# rpi64.net
KiCad netlist of a schematic drawn in EAGLE
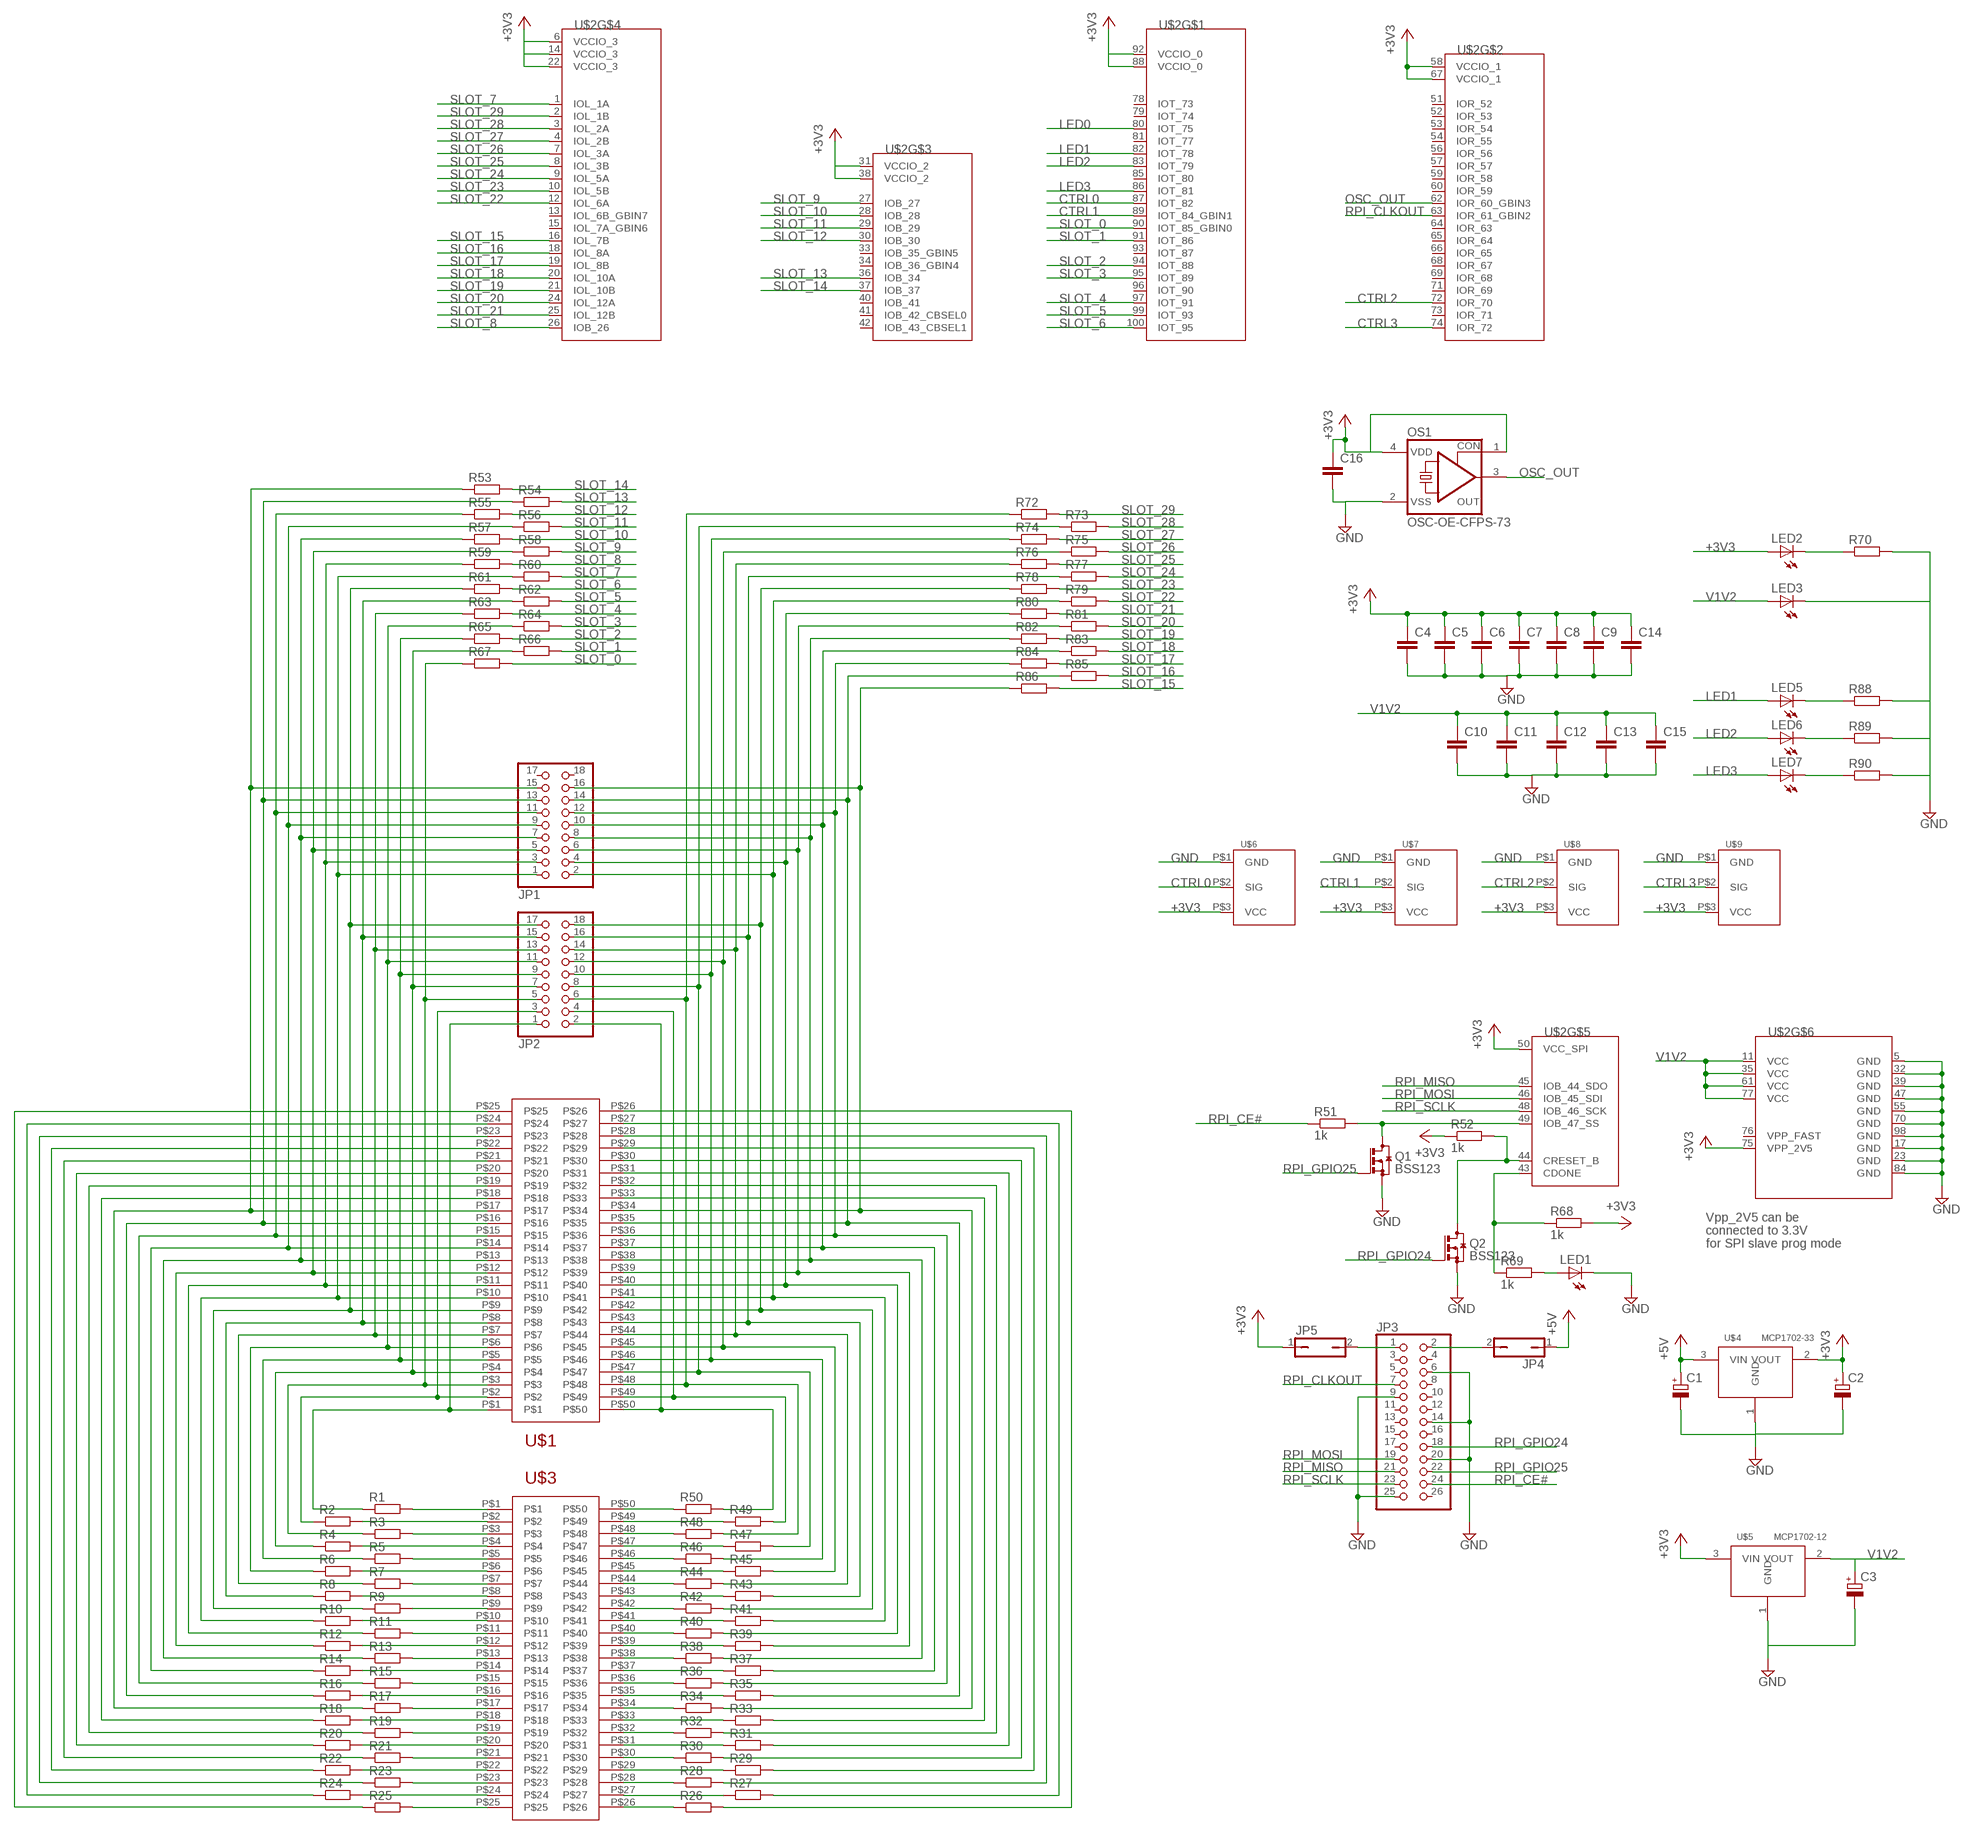
[diagram p0: schematic, sheet 1]

(export (version "E")
  (design (tool "Eeschema 10.0.6"))
  (components
    (comp (ref "C1")
      (value "CPOL-EUR/2012-12R")
      (footprint "eagle-import:R_2012-12R")
      (libsource (lib "eagle-import") (part "CPOL-EUR/2012-12R"))
    )
    (comp (ref "C2")
      (value "CPOL-EUR/2012-12R")
      (footprint "eagle-import:R_2012-12R")
      (libsource (lib "eagle-import") (part "CPOL-EUR/2012-12R"))
    )
    (comp (ref "C3")
      (value "CPOL-EUR/2012-12R")
      (footprint "eagle-import:R_2012-12R")
      (libsource (lib "eagle-import") (part "CPOL-EUR/2012-12R"))
    )
    (comp (ref "C4")
      (value "C-EUC0805")
      (footprint "eagle-import:C0805")
      (libsource (lib "eagle-import") (part "C-EUC0805"))
    )
    (comp (ref "C5")
      (value "C-EUC0805")
      (footprint "eagle-import:C0805")
      (libsource (lib "eagle-import") (part "C-EUC0805"))
    )
    (comp (ref "C6")
      (value "C-EUC0805")
      (footprint "eagle-import:C0805")
      (libsource (lib "eagle-import") (part "C-EUC0805"))
    )
    (comp (ref "C7")
      (value "C-EUC0805")
      (footprint "eagle-import:C0805")
      (libsource (lib "eagle-import") (part "C-EUC0805"))
    )
    (comp (ref "C8")
      (value "C-EUC0805")
      (footprint "eagle-import:C0805")
      (libsource (lib "eagle-import") (part "C-EUC0805"))
    )
    (comp (ref "C9")
      (value "C-EUC0805")
      (footprint "eagle-import:C0805")
      (libsource (lib "eagle-import") (part "C-EUC0805"))
    )
    (comp (ref "C10")
      (value "C-EUC0805")
      (footprint "eagle-import:C0805")
      (libsource (lib "eagle-import") (part "C-EUC0805"))
    )
    (comp (ref "C11")
      (value "C-EUC0805")
      (footprint "eagle-import:C0805")
      (libsource (lib "eagle-import") (part "C-EUC0805"))
    )
    (comp (ref "C12")
      (value "C-EUC0805")
      (footprint "eagle-import:C0805")
      (libsource (lib "eagle-import") (part "C-EUC0805"))
    )
    (comp (ref "C13")
      (value "C-EUC0805")
      (footprint "eagle-import:C0805")
      (libsource (lib "eagle-import") (part "C-EUC0805"))
    )
    (comp (ref "C14")
      (value "C-EUC0805")
      (footprint "eagle-import:C0805")
      (libsource (lib "eagle-import") (part "C-EUC0805"))
    )
    (comp (ref "C15")
      (value "C-EUC0805")
      (footprint "eagle-import:C0805")
      (libsource (lib "eagle-import") (part "C-EUC0805"))
    )
    (comp (ref "C16")
      (value "C-EUC0805")
      (footprint "eagle-import:C0805")
      (libsource (lib "eagle-import") (part "C-EUC0805"))
    )
    (comp (ref "JP1")
      (value "PINHD-2X9")
      (footprint "eagle-import:2X09")
      (libsource (lib "eagle-import") (part "PINHD-2X9"))
    )
    (comp (ref "JP2")
      (value "PINHD-2X9")
      (footprint "eagle-import:2X09")
      (libsource (lib "eagle-import") (part "PINHD-2X9"))
    )
    (comp (ref "JP3")
      (value "PINHD-2X13")
      (footprint "eagle-import:2X13")
      (libsource (lib "eagle-import") (part "PINHD-2X13"))
    )
    (comp (ref "JP4")
      (value "JP1Q")
      (footprint "eagle-import:JP1")
      (libsource (lib "eagle-import") (part "JP1Q"))
    )
    (comp (ref "JP5")
      (value "JP1Q")
      (footprint "eagle-import:JP1")
      (libsource (lib "eagle-import") (part "JP1Q"))
    )
    (comp (ref "LED1")
      (value "LEDCHIPLED_0603")
      (footprint "eagle-import:CHIPLED_0603")
      (libsource (lib "eagle-import") (part "LEDCHIPLED_0603"))
    )
    (comp (ref "LED2")
      (value "LEDCHIPLED_0603")
      (footprint "eagle-import:CHIPLED_0603")
      (libsource (lib "eagle-import") (part "LEDCHIPLED_0603"))
    )
    (comp (ref "LED3")
      (value "LEDCHIPLED_0603")
      (footprint "eagle-import:CHIPLED_0603")
      (libsource (lib "eagle-import") (part "LEDCHIPLED_0603"))
    )
    (comp (ref "LED5")
      (value "LEDCHIPLED_0603")
      (footprint "eagle-import:CHIPLED_0603")
      (libsource (lib "eagle-import") (part "LEDCHIPLED_0603"))
    )
    (comp (ref "LED6")
      (value "LEDCHIPLED_0603")
      (footprint "eagle-import:CHIPLED_0603")
      (libsource (lib "eagle-import") (part "LEDCHIPLED_0603"))
    )
    (comp (ref "LED7")
      (value "LEDCHIPLED_0603")
      (footprint "eagle-import:CHIPLED_0603")
      (libsource (lib "eagle-import") (part "LEDCHIPLED_0603"))
    )
    (comp (ref "OS1")
      (value "OSC-OE-CFPS-73")
      (footprint "eagle-import:7.2X5.2-4-PAD")
      (libsource (lib "eagle-import") (part "OSC-OE-CFPS-73"))
    )
    (comp (ref "Q1")
      (value "BSS123")
      (footprint "eagle-import:SOT23")
      (libsource (lib "eagle-import") (part "BSS123"))
    )
    (comp (ref "Q2")
      (value "BSS123")
      (footprint "eagle-import:SOT23")
      (libsource (lib "eagle-import") (part "BSS123"))
    )
    (comp (ref "R1")
      (value "R-EU_R0603")
      (footprint "eagle-import:R0603")
      (libsource (lib "eagle-import") (part "R-EU_R0603"))
    )
    (comp (ref "R2")
      (value "R-EU_R0603")
      (footprint "eagle-import:R0603")
      (libsource (lib "eagle-import") (part "R-EU_R0603"))
    )
    (comp (ref "R3")
      (value "R-EU_R0603")
      (footprint "eagle-import:R0603")
      (libsource (lib "eagle-import") (part "R-EU_R0603"))
    )
    (comp (ref "R4")
      (value "R-EU_R0603")
      (footprint "eagle-import:R0603")
      (libsource (lib "eagle-import") (part "R-EU_R0603"))
    )
    (comp (ref "R5")
      (value "R-EU_R0603")
      (footprint "eagle-import:R0603")
      (libsource (lib "eagle-import") (part "R-EU_R0603"))
    )
    (comp (ref "R6")
      (value "R-EU_R0603")
      (footprint "eagle-import:R0603")
      (libsource (lib "eagle-import") (part "R-EU_R0603"))
    )
    (comp (ref "R7")
      (value "R-EU_R0603")
      (footprint "eagle-import:R0603")
      (libsource (lib "eagle-import") (part "R-EU_R0603"))
    )
    (comp (ref "R8")
      (value "R-EU_R0603")
      (footprint "eagle-import:R0603")
      (libsource (lib "eagle-import") (part "R-EU_R0603"))
    )
    (comp (ref "R9")
      (value "R-EU_R0603")
      (footprint "eagle-import:R0603")
      (libsource (lib "eagle-import") (part "R-EU_R0603"))
    )
    (comp (ref "R10")
      (value "R-EU_R0603")
      (footprint "eagle-import:R0603")
      (libsource (lib "eagle-import") (part "R-EU_R0603"))
    )
    (comp (ref "R11")
      (value "R-EU_R0603")
      (footprint "eagle-import:R0603")
      (libsource (lib "eagle-import") (part "R-EU_R0603"))
    )
    (comp (ref "R12")
      (value "R-EU_R0603")
      (footprint "eagle-import:R0603")
      (libsource (lib "eagle-import") (part "R-EU_R0603"))
    )
    (comp (ref "R13")
      (value "R-EU_R0603")
      (footprint "eagle-import:R0603")
      (libsource (lib "eagle-import") (part "R-EU_R0603"))
    )
    (comp (ref "R14")
      (value "R-EU_R0603")
      (footprint "eagle-import:R0603")
      (libsource (lib "eagle-import") (part "R-EU_R0603"))
    )
    (comp (ref "R15")
      (value "R-EU_R0603")
      (footprint "eagle-import:R0603")
      (libsource (lib "eagle-import") (part "R-EU_R0603"))
    )
    (comp (ref "R16")
      (value "R-EU_R0603")
      (footprint "eagle-import:R0603")
      (libsource (lib "eagle-import") (part "R-EU_R0603"))
    )
    (comp (ref "R17")
      (value "R-EU_R0603")
      (footprint "eagle-import:R0603")
      (libsource (lib "eagle-import") (part "R-EU_R0603"))
    )
    (comp (ref "R18")
      (value "R-EU_R0603")
      (footprint "eagle-import:R0603")
      (libsource (lib "eagle-import") (part "R-EU_R0603"))
    )
    (comp (ref "R19")
      (value "R-EU_R0603")
      (footprint "eagle-import:R0603")
      (libsource (lib "eagle-import") (part "R-EU_R0603"))
    )
    (comp (ref "R20")
      (value "R-EU_R0603")
      (footprint "eagle-import:R0603")
      (libsource (lib "eagle-import") (part "R-EU_R0603"))
    )
    (comp (ref "R21")
      (value "R-EU_R0603")
      (footprint "eagle-import:R0603")
      (libsource (lib "eagle-import") (part "R-EU_R0603"))
    )
    (comp (ref "R22")
      (value "R-EU_R0603")
      (footprint "eagle-import:R0603")
      (libsource (lib "eagle-import") (part "R-EU_R0603"))
    )
    (comp (ref "R23")
      (value "R-EU_R0603")
      (footprint "eagle-import:R0603")
      (libsource (lib "eagle-import") (part "R-EU_R0603"))
    )
    (comp (ref "R24")
      (value "R-EU_R0603")
      (footprint "eagle-import:R0603")
      (libsource (lib "eagle-import") (part "R-EU_R0603"))
    )
    (comp (ref "R25")
      (value "R-EU_R0603")
      (footprint "eagle-import:R0603")
      (libsource (lib "eagle-import") (part "R-EU_R0603"))
    )
    (comp (ref "R26")
      (value "R-EU_R0603")
      (footprint "eagle-import:R0603")
      (libsource (lib "eagle-import") (part "R-EU_R0603"))
    )
    (comp (ref "R27")
      (value "R-EU_R0603")
      (footprint "eagle-import:R0603")
      (libsource (lib "eagle-import") (part "R-EU_R0603"))
    )
    (comp (ref "R28")
      (value "R-EU_R0603")
      (footprint "eagle-import:R0603")
      (libsource (lib "eagle-import") (part "R-EU_R0603"))
    )
    (comp (ref "R29")
      (value "R-EU_R0603")
      (footprint "eagle-import:R0603")
      (libsource (lib "eagle-import") (part "R-EU_R0603"))
    )
    (comp (ref "R30")
      (value "R-EU_R0603")
      (footprint "eagle-import:R0603")
      (libsource (lib "eagle-import") (part "R-EU_R0603"))
    )
    (comp (ref "R31")
      (value "R-EU_R0603")
      (footprint "eagle-import:R0603")
      (libsource (lib "eagle-import") (part "R-EU_R0603"))
    )
    (comp (ref "R32")
      (value "R-EU_R0603")
      (footprint "eagle-import:R0603")
      (libsource (lib "eagle-import") (part "R-EU_R0603"))
    )
    (comp (ref "R33")
      (value "R-EU_R0603")
      (footprint "eagle-import:R0603")
      (libsource (lib "eagle-import") (part "R-EU_R0603"))
    )
    (comp (ref "R34")
      (value "R-EU_R0603")
      (footprint "eagle-import:R0603")
      (libsource (lib "eagle-import") (part "R-EU_R0603"))
    )
    (comp (ref "R35")
      (value "R-EU_R0603")
      (footprint "eagle-import:R0603")
      (libsource (lib "eagle-import") (part "R-EU_R0603"))
    )
    (comp (ref "R36")
      (value "R-EU_R0603")
      (footprint "eagle-import:R0603")
      (libsource (lib "eagle-import") (part "R-EU_R0603"))
    )
    (comp (ref "R37")
      (value "R-EU_R0603")
      (footprint "eagle-import:R0603")
      (libsource (lib "eagle-import") (part "R-EU_R0603"))
    )
    (comp (ref "R38")
      (value "R-EU_R0603")
      (footprint "eagle-import:R0603")
      (libsource (lib "eagle-import") (part "R-EU_R0603"))
    )
    (comp (ref "R39")
      (value "R-EU_R0603")
      (footprint "eagle-import:R0603")
      (libsource (lib "eagle-import") (part "R-EU_R0603"))
    )
    (comp (ref "R40")
      (value "R-EU_R0603")
      (footprint "eagle-import:R0603")
      (libsource (lib "eagle-import") (part "R-EU_R0603"))
    )
    (comp (ref "R41")
      (value "R-EU_R0603")
      (footprint "eagle-import:R0603")
      (libsource (lib "eagle-import") (part "R-EU_R0603"))
    )
    (comp (ref "R42")
      (value "R-EU_R0603")
      (footprint "eagle-import:R0603")
      (libsource (lib "eagle-import") (part "R-EU_R0603"))
    )
    (comp (ref "R43")
      (value "R-EU_R0603")
      (footprint "eagle-import:R0603")
      (libsource (lib "eagle-import") (part "R-EU_R0603"))
    )
    (comp (ref "R44")
      (value "R-EU_R0603")
      (footprint "eagle-import:R0603")
      (libsource (lib "eagle-import") (part "R-EU_R0603"))
    )
    (comp (ref "R45")
      (value "R-EU_R0603")
      (footprint "eagle-import:R0603")
      (libsource (lib "eagle-import") (part "R-EU_R0603"))
    )
    (comp (ref "R46")
      (value "R-EU_R0603")
      (footprint "eagle-import:R0603")
      (libsource (lib "eagle-import") (part "R-EU_R0603"))
    )
    (comp (ref "R47")
      (value "R-EU_R0603")
      (footprint "eagle-import:R0603")
      (libsource (lib "eagle-import") (part "R-EU_R0603"))
    )
    (comp (ref "R48")
      (value "R-EU_R0603")
      (footprint "eagle-import:R0603")
      (libsource (lib "eagle-import") (part "R-EU_R0603"))
    )
    (comp (ref "R49")
      (value "R-EU_R0603")
      (footprint "eagle-import:R0603")
      (libsource (lib "eagle-import") (part "R-EU_R0603"))
    )
    (comp (ref "R50")
      (value "R-EU_R0603")
      (footprint "eagle-import:R0603")
      (libsource (lib "eagle-import") (part "R-EU_R0603"))
    )
    (comp (ref "R51")
      (value "1k")
      (footprint "eagle-import:R0603")
      (libsource (lib "eagle-import") (part "R-EU_R0603"))
    )
    (comp (ref "R52")
      (value "1k")
      (footprint "eagle-import:R0603")
      (libsource (lib "eagle-import") (part "R-EU_R0603"))
    )
    (comp (ref "R53")
      (value "R-EU_R0603")
      (footprint "eagle-import:R0603")
      (libsource (lib "eagle-import") (part "R-EU_R0603"))
    )
    (comp (ref "R54")
      (value "R-EU_R0603")
      (footprint "eagle-import:R0603")
      (libsource (lib "eagle-import") (part "R-EU_R0603"))
    )
    (comp (ref "R55")
      (value "R-EU_R0603")
      (footprint "eagle-import:R0603")
      (libsource (lib "eagle-import") (part "R-EU_R0603"))
    )
    (comp (ref "R56")
      (value "R-EU_R0603")
      (footprint "eagle-import:R0603")
      (libsource (lib "eagle-import") (part "R-EU_R0603"))
    )
    (comp (ref "R57")
      (value "R-EU_R0603")
      (footprint "eagle-import:R0603")
      (libsource (lib "eagle-import") (part "R-EU_R0603"))
    )
    (comp (ref "R58")
      (value "R-EU_R0603")
      (footprint "eagle-import:R0603")
      (libsource (lib "eagle-import") (part "R-EU_R0603"))
    )
    (comp (ref "R59")
      (value "R-EU_R0603")
      (footprint "eagle-import:R0603")
      (libsource (lib "eagle-import") (part "R-EU_R0603"))
    )
    (comp (ref "R60")
      (value "R-EU_R0603")
      (footprint "eagle-import:R0603")
      (libsource (lib "eagle-import") (part "R-EU_R0603"))
    )
    (comp (ref "R61")
      (value "R-EU_R0603")
      (footprint "eagle-import:R0603")
      (libsource (lib "eagle-import") (part "R-EU_R0603"))
    )
    (comp (ref "R62")
      (value "R-EU_R0603")
      (footprint "eagle-import:R0603")
      (libsource (lib "eagle-import") (part "R-EU_R0603"))
    )
    (comp (ref "R63")
      (value "R-EU_R0603")
      (footprint "eagle-import:R0603")
      (libsource (lib "eagle-import") (part "R-EU_R0603"))
    )
    (comp (ref "R64")
      (value "R-EU_R0603")
      (footprint "eagle-import:R0603")
      (libsource (lib "eagle-import") (part "R-EU_R0603"))
    )
    (comp (ref "R65")
      (value "R-EU_R0603")
      (footprint "eagle-import:R0603")
      (libsource (lib "eagle-import") (part "R-EU_R0603"))
    )
    (comp (ref "R66")
      (value "R-EU_R0603")
      (footprint "eagle-import:R0603")
      (libsource (lib "eagle-import") (part "R-EU_R0603"))
    )
    (comp (ref "R67")
      (value "R-EU_R0603")
      (footprint "eagle-import:R0603")
      (libsource (lib "eagle-import") (part "R-EU_R0603"))
    )
    (comp (ref "R68")
      (value "1k")
      (footprint "eagle-import:R0603")
      (libsource (lib "eagle-import") (part "R-EU_R0603"))
    )
    (comp (ref "R69")
      (value "1k")
      (footprint "eagle-import:R0603")
      (libsource (lib "eagle-import") (part "R-EU_R0603"))
    )
    (comp (ref "R70")
      (value "R-EU_R0603")
      (footprint "eagle-import:R0603")
      (libsource (lib "eagle-import") (part "R-EU_R0603"))
    )
    (comp (ref "R72")
      (value "R-EU_R0603")
      (footprint "eagle-import:R0603")
      (libsource (lib "eagle-import") (part "R-EU_R0603"))
    )
    (comp (ref "R73")
      (value "R-EU_R0603")
      (footprint "eagle-import:R0603")
      (libsource (lib "eagle-import") (part "R-EU_R0603"))
    )
    (comp (ref "R74")
      (value "R-EU_R0603")
      (footprint "eagle-import:R0603")
      (libsource (lib "eagle-import") (part "R-EU_R0603"))
    )
    (comp (ref "R75")
      (value "R-EU_R0603")
      (footprint "eagle-import:R0603")
      (libsource (lib "eagle-import") (part "R-EU_R0603"))
    )
    (comp (ref "R76")
      (value "R-EU_R0603")
      (footprint "eagle-import:R0603")
      (libsource (lib "eagle-import") (part "R-EU_R0603"))
    )
    (comp (ref "R77")
      (value "R-EU_R0603")
      (footprint "eagle-import:R0603")
      (libsource (lib "eagle-import") (part "R-EU_R0603"))
    )
    (comp (ref "R78")
      (value "R-EU_R0603")
      (footprint "eagle-import:R0603")
      (libsource (lib "eagle-import") (part "R-EU_R0603"))
    )
    (comp (ref "R79")
      (value "R-EU_R0603")
      (footprint "eagle-import:R0603")
      (libsource (lib "eagle-import") (part "R-EU_R0603"))
    )
    (comp (ref "R80")
      (value "R-EU_R0603")
      (footprint "eagle-import:R0603")
      (libsource (lib "eagle-import") (part "R-EU_R0603"))
    )
    (comp (ref "R81")
      (value "R-EU_R0603")
      (footprint "eagle-import:R0603")
      (libsource (lib "eagle-import") (part "R-EU_R0603"))
    )
    (comp (ref "R82")
      (value "R-EU_R0603")
      (footprint "eagle-import:R0603")
      (libsource (lib "eagle-import") (part "R-EU_R0603"))
    )
    (comp (ref "R83")
      (value "R-EU_R0603")
      (footprint "eagle-import:R0603")
      (libsource (lib "eagle-import") (part "R-EU_R0603"))
    )
    (comp (ref "R84")
      (value "R-EU_R0603")
      (footprint "eagle-import:R0603")
      (libsource (lib "eagle-import") (part "R-EU_R0603"))
    )
    (comp (ref "R85")
      (value "R-EU_R0603")
      (footprint "eagle-import:R0603")
      (libsource (lib "eagle-import") (part "R-EU_R0603"))
    )
    (comp (ref "R86")
      (value "R-EU_R0603")
      (footprint "eagle-import:R0603")
      (libsource (lib "eagle-import") (part "R-EU_R0603"))
    )
    (comp (ref "R88")
      (value "R-EU_R0603")
      (footprint "eagle-import:R0603")
      (libsource (lib "eagle-import") (part "R-EU_R0603"))
    )
    (comp (ref "R89")
      (value "R-EU_R0603")
      (footprint "eagle-import:R0603")
      (libsource (lib "eagle-import") (part "R-EU_R0603"))
    )
    (comp (ref "R90")
      (value "R-EU_R0603")
      (footprint "eagle-import:R0603")
      (libsource (lib "eagle-import") (part "R-EU_R0603"))
    )
    (comp (ref "U$1")
      (value "5530843-5")
      (footprint "eagle-import:5530843-3")
      (libsource (lib "eagle-import") (part "5530843-5"))
    )
    (comp (ref "U$2")
      (value "ICE40HX1KVQ100")
      (footprint "eagle-import:VQ100")
      (libsource (lib "eagle-import") (part "ICE40HX1KVQ100"))
    )
    (comp (ref "U$3")
      (value "EDGE50")
      (footprint "eagle-import:EDGE50")
      (libsource (lib "eagle-import") (part "EDGE50"))
    )
    (comp (ref "U$4")
      (value "MCP1702-33")
      (footprint "eagle-import:SOT23A")
      (libsource (lib "eagle-import") (part "MCP1702"))
    )
    (comp (ref "U$5")
      (value "MCP1702-12")
      (footprint "eagle-import:SOT23A")
      (libsource (lib "eagle-import") (part "MCP1702"))
    )
    (comp (ref "U$6")
      (value "N64_CONTROLER")
      (footprint "eagle-import:N64_CONTROLER")
      (libsource (lib "eagle-import") (part "N64_CONTROLER"))
    )
    (comp (ref "U$7")
      (value "N64_CONTROLER")
      (footprint "eagle-import:N64_CONTROLER")
      (libsource (lib "eagle-import") (part "N64_CONTROLER"))
    )
    (comp (ref "U$8")
      (value "N64_CONTROLER")
      (footprint "eagle-import:N64_CONTROLER")
      (libsource (lib "eagle-import") (part "N64_CONTROLER"))
    )
    (comp (ref "U$9")
      (value "N64_CONTROLER")
      (footprint "eagle-import:N64_CONTROLER")
      (libsource (lib "eagle-import") (part "N64_CONTROLER"))
    )
  )
  (nets
    (net (code "1") (name "+3V3") (class "Default")
      (node (ref "C14") (pin "1") (pinfunction "1_1") (pintype "passive"))
      (node (ref "C16") (pin "1") (pinfunction "1_1") (pintype "passive"))
      (node (ref "C2") (pin "+") (pinfunction "+_+") (pintype "passive"))
      (node (ref "C4") (pin "1") (pinfunction "1_1") (pintype "passive"))
      (node (ref "C5") (pin "1") (pinfunction "1_1") (pintype "passive"))
      (node (ref "C6") (pin "1") (pinfunction "1_1") (pintype "passive"))
      (node (ref "C7") (pin "1") (pinfunction "1_1") (pintype "passive"))
      (node (ref "C8") (pin "1") (pinfunction "1_1") (pintype "passive"))
      (node (ref "C9") (pin "1") (pinfunction "1_1") (pintype "passive"))
      (node (ref "JP5") (pin "1") (pinfunction "1_1") (pintype "passive"))
      (node (ref "LED2") (pin "A") (pinfunction "A_A") (pintype "passive"))
      (node (ref "OS1") (pin "1") (pinfunction "CON_1") (pintype "input"))
      (node (ref "OS1") (pin "4") (pinfunction "VDD_4") (pintype "power_in"))
      (node (ref "R52") (pin "1") (pinfunction "1_1") (pintype "passive"))
      (node (ref "R68") (pin "2") (pinfunction "2_2") (pintype "passive"))
      (node (ref "U$2") (pin "14") (pinfunction "VCCIO_3_14") (pintype "power_in"))
      (node (ref "U$2") (pin "22") (pinfunction "VCCIO_3_22") (pintype "power_in"))
      (node (ref "U$2") (pin "31") (pinfunction "VCCIO_2_31") (pintype "power_in"))
      (node (ref "U$2") (pin "38") (pinfunction "VCCIO_2_38") (pintype "power_in"))
      (node (ref "U$2") (pin "50") (pinfunction "VCC_SPI_50") (pintype "power_in"))
      (node (ref "U$2") (pin "58") (pinfunction "VCCIO_1_58") (pintype "power_in"))
      (node (ref "U$2") (pin "6") (pinfunction "VCCIO_3_6") (pintype "power_in"))
      (node (ref "U$2") (pin "67") (pinfunction "VCCIO_1_67") (pintype "power_in"))
      (node (ref "U$2") (pin "75") (pinfunction "VPP_2V5_75") (pintype "power_in"))
      (node (ref "U$2") (pin "88") (pinfunction "VCCIO_0_88") (pintype "power_in"))
      (node (ref "U$2") (pin "92") (pinfunction "VCCIO_0_92") (pintype "power_in"))
      (node (ref "U$4") (pin "2") (pinfunction "VOUT_2") (pintype "bidirectional"))
      (node (ref "U$5") (pin "3") (pinfunction "VIN_3") (pintype "bidirectional"))
      (node (ref "U$6") (pin "P$3") (pinfunction "VCC_P$3") (pintype "power_in"))
      (node (ref "U$7") (pin "P$3") (pinfunction "VCC_P$3") (pintype "power_in"))
      (node (ref "U$8") (pin "P$3") (pinfunction "VCC_P$3") (pintype "power_in"))
      (node (ref "U$9") (pin "P$3") (pinfunction "VCC_P$3") (pintype "power_in"))
    )
    (net (code "2") (name "+5V") (class "Default")
      (node (ref "C1") (pin "+") (pinfunction "+_+") (pintype "passive"))
      (node (ref "JP4") (pin "1") (pinfunction "1_1") (pintype "passive"))
      (node (ref "U$4") (pin "3") (pinfunction "VIN_3") (pintype "bidirectional"))
    )
    (net (code "3") (name "/CTRL0") (class "Default")
      (node (ref "U$2") (pin "87") (pinfunction "IOT_82_87") (pintype "bidirectional"))
      (node (ref "U$6") (pin "P$2") (pinfunction "SIG_P$2") (pintype "power_in"))
    )
    (net (code "4") (name "/CTRL1") (class "Default")
      (node (ref "U$2") (pin "89") (pinfunction "IOT_84_GBIN1_89") (pintype "bidirectional"))
      (node (ref "U$7") (pin "P$2") (pinfunction "SIG_P$2") (pintype "power_in"))
    )
    (net (code "5") (name "/CTRL2") (class "Default")
      (node (ref "U$2") (pin "72") (pinfunction "IOR_70_72") (pintype "bidirectional"))
      (node (ref "U$8") (pin "P$2") (pinfunction "SIG_P$2") (pintype "power_in"))
    )
    (net (code "6") (name "/CTRL3") (class "Default")
      (node (ref "U$2") (pin "74") (pinfunction "IOR_72_74") (pintype "bidirectional"))
      (node (ref "U$9") (pin "P$2") (pinfunction "SIG_P$2") (pintype "power_in"))
    )
    (net (code "7") (name "/LED0") (class "Default")
      (node (ref "U$2") (pin "80") (pinfunction "IOT_75_80") (pintype "bidirectional"))
    )
    (net (code "8") (name "/LED1") (class "Default")
      (node (ref "LED5") (pin "A") (pinfunction "A_A") (pintype "passive"))
      (node (ref "U$2") (pin "82") (pinfunction "IOT_78_82") (pintype "bidirectional"))
    )
    (net (code "9") (name "/LED2") (class "Default")
      (node (ref "LED6") (pin "A") (pinfunction "A_A") (pintype "passive"))
      (node (ref "U$2") (pin "83") (pinfunction "IOT_79_83") (pintype "bidirectional"))
    )
    (net (code "10") (name "/LED3") (class "Default")
      (node (ref "LED7") (pin "A") (pinfunction "A_A") (pintype "passive"))
      (node (ref "U$2") (pin "86") (pinfunction "IOT_81_86") (pintype "bidirectional"))
    )
    (net (code "11") (name "/OSC_OUT") (class "Default")
      (node (ref "OS1") (pin "3") (pinfunction "OUT_3") (pintype "output"))
      (node (ref "U$2") (pin "62") (pinfunction "IOR_60_GBIN3_62") (pintype "bidirectional"))
    )
    (net (code "12") (name "/RPI_CE#") (class "Default")
      (node (ref "JP3") (pin "24") (pinfunction "24_24") (pintype "passive"))
      (node (ref "R51") (pin "1") (pinfunction "1_1") (pintype "passive"))
    )
    (net (code "13") (name "/RPI_CLKOUT") (class "Default")
      (node (ref "JP3") (pin "7") (pinfunction "7_7") (pintype "passive"))
      (node (ref "U$2") (pin "63") (pinfunction "IOR_61_GBIN2_63") (pintype "bidirectional"))
    )
    (net (code "14") (name "/RPI_GPIO24") (class "Default")
      (node (ref "JP3") (pin "18") (pinfunction "18_18") (pintype "passive"))
      (node (ref "Q2") (pin "1") (pinfunction "G_1") (pintype "passive"))
    )
    (net (code "15") (name "/RPI_GPIO25") (class "Default")
      (node (ref "JP3") (pin "22") (pinfunction "22_22") (pintype "passive"))
      (node (ref "Q1") (pin "1") (pinfunction "G_1") (pintype "passive"))
    )
    (net (code "16") (name "/RPI_MISO") (class "Default")
      (node (ref "JP3") (pin "21") (pinfunction "21_21") (pintype "passive"))
      (node (ref "U$2") (pin "45") (pinfunction "IOB_44_SDO_45") (pintype "bidirectional"))
    )
    (net (code "17") (name "/RPI_MOSI") (class "Default")
      (node (ref "JP3") (pin "19") (pinfunction "19_19") (pintype "passive"))
      (node (ref "U$2") (pin "46") (pinfunction "IOB_45_SDI_46") (pintype "bidirectional"))
    )
    (net (code "18") (name "/RPI_SCLK") (class "Default")
      (node (ref "JP3") (pin "23") (pinfunction "23_23") (pintype "passive"))
      (node (ref "U$2") (pin "48") (pinfunction "IOB_46_SCK_48") (pintype "bidirectional"))
    )
    (net (code "19") (name "/SLOT_0") (class "Default")
      (node (ref "R67") (pin "2") (pinfunction "2_2") (pintype "passive"))
      (node (ref "U$2") (pin "90") (pinfunction "IOT_85_GBIN0_90") (pintype "bidirectional"))
    )
    (net (code "20") (name "/SLOT_1") (class "Default")
      (node (ref "R66") (pin "2") (pinfunction "2_2") (pintype "passive"))
      (node (ref "U$2") (pin "91") (pinfunction "IOT_86_91") (pintype "bidirectional"))
    )
    (net (code "21") (name "/SLOT_2") (class "Default")
      (node (ref "R65") (pin "2") (pinfunction "2_2") (pintype "passive"))
      (node (ref "U$2") (pin "94") (pinfunction "IOT_88_94") (pintype "bidirectional"))
    )
    (net (code "22") (name "/SLOT_3") (class "Default")
      (node (ref "R64") (pin "2") (pinfunction "2_2") (pintype "passive"))
      (node (ref "U$2") (pin "95") (pinfunction "IOT_89_95") (pintype "bidirectional"))
    )
    (net (code "23") (name "/SLOT_4") (class "Default")
      (node (ref "R63") (pin "2") (pinfunction "2_2") (pintype "passive"))
      (node (ref "U$2") (pin "97") (pinfunction "IOT_91_97") (pintype "bidirectional"))
    )
    (net (code "24") (name "/SLOT_5") (class "Default")
      (node (ref "R62") (pin "2") (pinfunction "2_2") (pintype "passive"))
      (node (ref "U$2") (pin "99") (pinfunction "IOT_93_99") (pintype "bidirectional"))
    )
    (net (code "25") (name "/SLOT_6") (class "Default")
      (node (ref "R61") (pin "2") (pinfunction "2_2") (pintype "passive"))
      (node (ref "U$2") (pin "100") (pinfunction "IOT_95_100") (pintype "bidirectional"))
    )
    (net (code "26") (name "/SLOT_7") (class "Default")
      (node (ref "R60") (pin "2") (pinfunction "2_2") (pintype "passive"))
      (node (ref "U$2") (pin "1") (pinfunction "IOL_1A_1") (pintype "bidirectional"))
    )
    (net (code "27") (name "/SLOT_8") (class "Default")
      (node (ref "R59") (pin "2") (pinfunction "2_2") (pintype "passive"))
      (node (ref "U$2") (pin "26") (pinfunction "IOB_26_26") (pintype "bidirectional"))
    )
    (net (code "28") (name "/SLOT_9") (class "Default")
      (node (ref "R58") (pin "2") (pinfunction "2_2") (pintype "passive"))
      (node (ref "U$2") (pin "27") (pinfunction "IOB_27_27") (pintype "bidirectional"))
    )
    (net (code "29") (name "/SLOT_10") (class "Default")
      (node (ref "R57") (pin "2") (pinfunction "2_2") (pintype "passive"))
      (node (ref "U$2") (pin "28") (pinfunction "IOB_28_28") (pintype "bidirectional"))
    )
    (net (code "30") (name "/SLOT_11") (class "Default")
      (node (ref "R56") (pin "2") (pinfunction "2_2") (pintype "passive"))
      (node (ref "U$2") (pin "29") (pinfunction "IOB_29_29") (pintype "bidirectional"))
    )
    (net (code "31") (name "/SLOT_12") (class "Default")
      (node (ref "R55") (pin "2") (pinfunction "2_2") (pintype "passive"))
      (node (ref "U$2") (pin "30") (pinfunction "IOB_30_30") (pintype "bidirectional"))
    )
    (net (code "32") (name "/SLOT_13") (class "Default")
      (node (ref "R54") (pin "2") (pinfunction "2_2") (pintype "passive"))
      (node (ref "U$2") (pin "36") (pinfunction "IOB_34_36") (pintype "bidirectional"))
    )
    (net (code "33") (name "/SLOT_14") (class "Default")
      (node (ref "R53") (pin "2") (pinfunction "2_2") (pintype "passive"))
      (node (ref "U$2") (pin "37") (pinfunction "IOB_37_37") (pintype "bidirectional"))
    )
    (net (code "34") (name "/SLOT_15") (class "Default")
      (node (ref "R86") (pin "2") (pinfunction "2_2") (pintype "passive"))
      (node (ref "U$2") (pin "16") (pinfunction "IOL_7B_16") (pintype "bidirectional"))
    )
    (net (code "35") (name "/SLOT_16") (class "Default")
      (node (ref "R85") (pin "2") (pinfunction "2_2") (pintype "passive"))
      (node (ref "U$2") (pin "18") (pinfunction "IOL_8A_18") (pintype "bidirectional"))
    )
    (net (code "36") (name "/SLOT_17") (class "Default")
      (node (ref "R84") (pin "2") (pinfunction "2_2") (pintype "passive"))
      (node (ref "U$2") (pin "19") (pinfunction "IOL_8B_19") (pintype "bidirectional"))
    )
    (net (code "37") (name "/SLOT_18") (class "Default")
      (node (ref "R83") (pin "2") (pinfunction "2_2") (pintype "passive"))
      (node (ref "U$2") (pin "20") (pinfunction "IOL_10A_20") (pintype "bidirectional"))
    )
    (net (code "38") (name "/SLOT_19") (class "Default")
      (node (ref "R82") (pin "2") (pinfunction "2_2") (pintype "passive"))
      (node (ref "U$2") (pin "21") (pinfunction "IOL_10B_21") (pintype "bidirectional"))
    )
    (net (code "39") (name "/SLOT_20") (class "Default")
      (node (ref "R81") (pin "2") (pinfunction "2_2") (pintype "passive"))
      (node (ref "U$2") (pin "24") (pinfunction "IOL_12A_24") (pintype "bidirectional"))
    )
    (net (code "40") (name "/SLOT_21") (class "Default")
      (node (ref "R80") (pin "2") (pinfunction "2_2") (pintype "passive"))
      (node (ref "U$2") (pin "25") (pinfunction "IOL_12B_25") (pintype "bidirectional"))
    )
    (net (code "41") (name "/SLOT_22") (class "Default")
      (node (ref "R79") (pin "2") (pinfunction "2_2") (pintype "passive"))
      (node (ref "U$2") (pin "12") (pinfunction "IOL_6A_12") (pintype "bidirectional"))
    )
    (net (code "42") (name "/SLOT_23") (class "Default")
      (node (ref "R78") (pin "2") (pinfunction "2_2") (pintype "passive"))
      (node (ref "U$2") (pin "10") (pinfunction "IOL_5B_10") (pintype "bidirectional"))
    )
    (net (code "43") (name "/SLOT_24") (class "Default")
      (node (ref "R77") (pin "2") (pinfunction "2_2") (pintype "passive"))
      (node (ref "U$2") (pin "9") (pinfunction "IOL_5A_9") (pintype "bidirectional"))
    )
    (net (code "44") (name "/SLOT_25") (class "Default")
      (node (ref "R76") (pin "2") (pinfunction "2_2") (pintype "passive"))
      (node (ref "U$2") (pin "8") (pinfunction "IOL_3B_8") (pintype "bidirectional"))
    )
    (net (code "45") (name "/SLOT_26") (class "Default")
      (node (ref "R75") (pin "2") (pinfunction "2_2") (pintype "passive"))
      (node (ref "U$2") (pin "7") (pinfunction "IOL_3A_7") (pintype "bidirectional"))
    )
    (net (code "46") (name "/SLOT_27") (class "Default")
      (node (ref "R74") (pin "2") (pinfunction "2_2") (pintype "passive"))
      (node (ref "U$2") (pin "4") (pinfunction "IOL_2B_4") (pintype "bidirectional"))
    )
    (net (code "47") (name "/SLOT_28") (class "Default")
      (node (ref "R73") (pin "2") (pinfunction "2_2") (pintype "passive"))
      (node (ref "U$2") (pin "3") (pinfunction "IOL_2A_3") (pintype "bidirectional"))
    )
    (net (code "48") (name "/SLOT_29") (class "Default")
      (node (ref "R72") (pin "2") (pinfunction "2_2") (pintype "passive"))
      (node (ref "U$2") (pin "2") (pinfunction "IOL_1B_2") (pintype "bidirectional"))
    )
    (net (code "49") (name "/V1V2") (class "Default")
      (node (ref "C10") (pin "1") (pinfunction "1_1") (pintype "passive"))
      (node (ref "C11") (pin "1") (pinfunction "1_1") (pintype "passive"))
      (node (ref "C12") (pin "1") (pinfunction "1_1") (pintype "passive"))
      (node (ref "C13") (pin "1") (pinfunction "1_1") (pintype "passive"))
      (node (ref "C15") (pin "1") (pinfunction "1_1") (pintype "passive"))
      (node (ref "C3") (pin "+") (pinfunction "+_+") (pintype "passive"))
      (node (ref "LED3") (pin "A") (pinfunction "A_A") (pintype "passive"))
      (node (ref "U$2") (pin "11") (pinfunction "VCC_11") (pintype "power_in"))
      (node (ref "U$2") (pin "35") (pinfunction "VCC_35") (pintype "power_in"))
      (node (ref "U$2") (pin "61") (pinfunction "VCC_61") (pintype "power_in"))
      (node (ref "U$2") (pin "77") (pinfunction "VCC_77") (pintype "power_in"))
      (node (ref "U$5") (pin "2") (pinfunction "VOUT_2") (pintype "bidirectional"))
    )
    (net (code "50") (name "/VPP_FAST") (class "Default")
      (node (ref "U$2") (pin "76") (pinfunction "VPP_FAST_76") (pintype "power_in"))
    )
    (net (code "51") (name "GND") (class "Default")
      (node (ref "C1") (pin "-") (pinfunction "-_-") (pintype "passive"))
      (node (ref "C10") (pin "2") (pinfunction "2_2") (pintype "passive"))
      (node (ref "C11") (pin "2") (pinfunction "2_2") (pintype "passive"))
      (node (ref "C12") (pin "2") (pinfunction "2_2") (pintype "passive"))
      (node (ref "C13") (pin "2") (pinfunction "2_2") (pintype "passive"))
      (node (ref "C14") (pin "2") (pinfunction "2_2") (pintype "passive"))
      (node (ref "C15") (pin "2") (pinfunction "2_2") (pintype "passive"))
      (node (ref "C16") (pin "2") (pinfunction "2_2") (pintype "passive"))
      (node (ref "C2") (pin "-") (pinfunction "-_-") (pintype "passive"))
      (node (ref "C3") (pin "-") (pinfunction "-_-") (pintype "passive"))
      (node (ref "C4") (pin "2") (pinfunction "2_2") (pintype "passive"))
      (node (ref "C5") (pin "2") (pinfunction "2_2") (pintype "passive"))
      (node (ref "C6") (pin "2") (pinfunction "2_2") (pintype "passive"))
      (node (ref "C7") (pin "2") (pinfunction "2_2") (pintype "passive"))
      (node (ref "C8") (pin "2") (pinfunction "2_2") (pintype "passive"))
      (node (ref "C9") (pin "2") (pinfunction "2_2") (pintype "passive"))
      (node (ref "JP3") (pin "14") (pinfunction "14_14") (pintype "passive"))
      (node (ref "JP3") (pin "20") (pinfunction "20_20") (pintype "passive"))
      (node (ref "JP3") (pin "25") (pinfunction "25_25") (pintype "passive"))
      (node (ref "JP3") (pin "6") (pinfunction "6_6") (pintype "passive"))
      (node (ref "JP3") (pin "9") (pinfunction "9_9") (pintype "passive"))
      (node (ref "LED1") (pin "C") (pinfunction "C_C") (pintype "passive"))
      (node (ref "LED3") (pin "C") (pinfunction "C_C") (pintype "passive"))
      (node (ref "OS1") (pin "2") (pinfunction "VSS_2") (pintype "power_in"))
      (node (ref "Q1") (pin "2") (pinfunction "S_2") (pintype "passive"))
      (node (ref "Q2") (pin "2") (pinfunction "S_2") (pintype "passive"))
      (node (ref "R70") (pin "2") (pinfunction "2_2") (pintype "passive"))
      (node (ref "R88") (pin "2") (pinfunction "2_2") (pintype "passive"))
      (node (ref "R89") (pin "2") (pinfunction "2_2") (pintype "passive"))
      (node (ref "R90") (pin "2") (pinfunction "2_2") (pintype "passive"))
      (node (ref "U$2") (pin "17") (pinfunction "GND_17") (pintype "power_in"))
      (node (ref "U$2") (pin "23") (pinfunction "GND_23") (pintype "power_in"))
      (node (ref "U$2") (pin "32") (pinfunction "GND_32") (pintype "power_in"))
      (node (ref "U$2") (pin "39") (pinfunction "GND_39") (pintype "power_in"))
      (node (ref "U$2") (pin "47") (pinfunction "GND_47") (pintype "power_in"))
      (node (ref "U$2") (pin "5") (pinfunction "GND_5") (pintype "power_in"))
      (node (ref "U$2") (pin "55") (pinfunction "GND_55") (pintype "power_in"))
      (node (ref "U$2") (pin "70") (pinfunction "GND_70") (pintype "power_in"))
      (node (ref "U$2") (pin "84") (pinfunction "GND_84") (pintype "power_in"))
      (node (ref "U$2") (pin "98") (pinfunction "GND_98") (pintype "power_in"))
      (node (ref "U$4") (pin "1") (pinfunction "GND_1") (pintype "bidirectional"))
      (node (ref "U$5") (pin "1") (pinfunction "GND_1") (pintype "bidirectional"))
      (node (ref "U$6") (pin "P$1") (pinfunction "GND_P$1") (pintype "power_in"))
      (node (ref "U$7") (pin "P$1") (pinfunction "GND_P$1") (pintype "power_in"))
      (node (ref "U$8") (pin "P$1") (pinfunction "GND_P$1") (pintype "power_in"))
      (node (ref "U$9") (pin "P$1") (pinfunction "GND_P$1") (pintype "power_in"))
    )
    (net (code "52") (name "Net-(JP1-Pad1)") (class "Default")
      (node (ref "JP1") (pin "1") (pinfunction "1_1") (pintype "passive"))
      (node (ref "R10") (pin "1") (pinfunction "1_1") (pintype "passive"))
      (node (ref "R60") (pin "1") (pinfunction "1_1") (pintype "passive"))
      (node (ref "U$1") (pin "P$10") (pinfunction "P$10_P$10") (pintype "bidirectional"))
    )
    (net (code "53") (name "Net-(JP1-Pad2)") (class "Default")
      (node (ref "JP1") (pin "2") (pinfunction "2_2") (pintype "passive"))
      (node (ref "R41") (pin "2") (pinfunction "2_2") (pintype "passive"))
      (node (ref "R79") (pin "1") (pinfunction "1_1") (pintype "passive"))
      (node (ref "U$1") (pin "P$41") (pinfunction "P$41_P$41") (pintype "bidirectional"))
    )
    (net (code "54") (name "Net-(JP1-Pad3)") (class "Default")
      (node (ref "JP1") (pin "3") (pinfunction "3_3") (pintype "passive"))
      (node (ref "R11") (pin "1") (pinfunction "1_1") (pintype "passive"))
      (node (ref "R59") (pin "1") (pinfunction "1_1") (pintype "passive"))
      (node (ref "U$1") (pin "P$11") (pinfunction "P$11_P$11") (pintype "bidirectional"))
    )
    (net (code "55") (name "Net-(JP1-Pad4)") (class "Default")
      (node (ref "JP1") (pin "4") (pinfunction "4_4") (pintype "passive"))
      (node (ref "R40") (pin "2") (pinfunction "2_2") (pintype "passive"))
      (node (ref "R80") (pin "1") (pinfunction "1_1") (pintype "passive"))
      (node (ref "U$1") (pin "P$40") (pinfunction "P$40_P$40") (pintype "bidirectional"))
    )
    (net (code "56") (name "Net-(JP1-Pad5)") (class "Default")
      (node (ref "JP1") (pin "5") (pinfunction "5_5") (pintype "passive"))
      (node (ref "R12") (pin "1") (pinfunction "1_1") (pintype "passive"))
      (node (ref "R58") (pin "1") (pinfunction "1_1") (pintype "passive"))
      (node (ref "U$1") (pin "P$12") (pinfunction "P$12_P$12") (pintype "bidirectional"))
    )
    (net (code "57") (name "Net-(JP1-Pad6)") (class "Default")
      (node (ref "JP1") (pin "6") (pinfunction "6_6") (pintype "passive"))
      (node (ref "R39") (pin "2") (pinfunction "2_2") (pintype "passive"))
      (node (ref "R81") (pin "1") (pinfunction "1_1") (pintype "passive"))
      (node (ref "U$1") (pin "P$39") (pinfunction "P$39_P$39") (pintype "bidirectional"))
    )
    (net (code "58") (name "Net-(JP1-Pad7)") (class "Default")
      (node (ref "JP1") (pin "7") (pinfunction "7_7") (pintype "passive"))
      (node (ref "R13") (pin "1") (pinfunction "1_1") (pintype "passive"))
      (node (ref "R57") (pin "1") (pinfunction "1_1") (pintype "passive"))
      (node (ref "U$1") (pin "P$13") (pinfunction "P$13_P$13") (pintype "bidirectional"))
    )
    (net (code "59") (name "Net-(JP1-Pad8)") (class "Default")
      (node (ref "JP1") (pin "8") (pinfunction "8_8") (pintype "passive"))
      (node (ref "R38") (pin "2") (pinfunction "2_2") (pintype "passive"))
      (node (ref "R82") (pin "1") (pinfunction "1_1") (pintype "passive"))
      (node (ref "U$1") (pin "P$38") (pinfunction "P$38_P$38") (pintype "bidirectional"))
    )
    (net (code "60") (name "Net-(JP1-Pad9)") (class "Default")
      (node (ref "JP1") (pin "9") (pinfunction "9_9") (pintype "passive"))
      (node (ref "R14") (pin "1") (pinfunction "1_1") (pintype "passive"))
      (node (ref "R56") (pin "1") (pinfunction "1_1") (pintype "passive"))
      (node (ref "U$1") (pin "P$14") (pinfunction "P$14_P$14") (pintype "bidirectional"))
    )
    (net (code "61") (name "Net-(JP1-Pad10)") (class "Default")
      (node (ref "JP1") (pin "10") (pinfunction "10_10") (pintype "passive"))
      (node (ref "R37") (pin "2") (pinfunction "2_2") (pintype "passive"))
      (node (ref "R83") (pin "1") (pinfunction "1_1") (pintype "passive"))
      (node (ref "U$1") (pin "P$37") (pinfunction "P$37_P$37") (pintype "bidirectional"))
    )
    (net (code "62") (name "Net-(JP1-Pad11)") (class "Default")
      (node (ref "JP1") (pin "11") (pinfunction "11_11") (pintype "passive"))
      (node (ref "R15") (pin "1") (pinfunction "1_1") (pintype "passive"))
      (node (ref "R55") (pin "1") (pinfunction "1_1") (pintype "passive"))
      (node (ref "U$1") (pin "P$15") (pinfunction "P$15_P$15") (pintype "bidirectional"))
    )
    (net (code "63") (name "Net-(JP1-Pad12)") (class "Default")
      (node (ref "JP1") (pin "12") (pinfunction "12_12") (pintype "passive"))
      (node (ref "R36") (pin "2") (pinfunction "2_2") (pintype "passive"))
      (node (ref "R84") (pin "1") (pinfunction "1_1") (pintype "passive"))
      (node (ref "U$1") (pin "P$36") (pinfunction "P$36_P$36") (pintype "bidirectional"))
    )
    (net (code "64") (name "Net-(JP1-Pad13)") (class "Default")
      (node (ref "JP1") (pin "13") (pinfunction "13_13") (pintype "passive"))
      (node (ref "R16") (pin "1") (pinfunction "1_1") (pintype "passive"))
      (node (ref "R54") (pin "1") (pinfunction "1_1") (pintype "passive"))
      (node (ref "U$1") (pin "P$16") (pinfunction "P$16_P$16") (pintype "bidirectional"))
    )
    (net (code "65") (name "Net-(JP1-Pad14)") (class "Default")
      (node (ref "JP1") (pin "14") (pinfunction "14_14") (pintype "passive"))
      (node (ref "R35") (pin "2") (pinfunction "2_2") (pintype "passive"))
      (node (ref "R85") (pin "1") (pinfunction "1_1") (pintype "passive"))
      (node (ref "U$1") (pin "P$35") (pinfunction "P$35_P$35") (pintype "bidirectional"))
    )
    (net (code "66") (name "Net-(JP1-Pad15)") (class "Default")
      (node (ref "JP1") (pin "15") (pinfunction "15_15") (pintype "passive"))
      (node (ref "R17") (pin "1") (pinfunction "1_1") (pintype "passive"))
      (node (ref "R53") (pin "1") (pinfunction "1_1") (pintype "passive"))
      (node (ref "U$1") (pin "P$17") (pinfunction "P$17_P$17") (pintype "bidirectional"))
    )
    (net (code "67") (name "Net-(JP1-Pad16)") (class "Default")
      (node (ref "JP1") (pin "16") (pinfunction "16_16") (pintype "passive"))
      (node (ref "R34") (pin "2") (pinfunction "2_2") (pintype "passive"))
      (node (ref "R86") (pin "1") (pinfunction "1_1") (pintype "passive"))
      (node (ref "U$1") (pin "P$34") (pinfunction "P$34_P$34") (pintype "bidirectional"))
    )
    (net (code "68") (name "Net-(JP2-Pad1)") (class "Default")
      (node (ref "JP2") (pin "1") (pinfunction "1_1") (pintype "passive"))
      (node (ref "R1") (pin "1") (pinfunction "1_1") (pintype "passive"))
      (node (ref "U$1") (pin "P$1") (pinfunction "P$1_P$1") (pintype "bidirectional"))
    )
    (net (code "69") (name "Net-(JP2-Pad2)") (class "Default")
      (node (ref "JP2") (pin "2") (pinfunction "2_2") (pintype "passive"))
      (node (ref "R50") (pin "2") (pinfunction "2_2") (pintype "passive"))
      (node (ref "U$1") (pin "P$50") (pinfunction "P$50_P$50") (pintype "bidirectional"))
    )
    (net (code "70") (name "Net-(JP2-Pad3)") (class "Default")
      (node (ref "JP2") (pin "3") (pinfunction "3_3") (pintype "passive"))
      (node (ref "R2") (pin "1") (pinfunction "1_1") (pintype "passive"))
      (node (ref "U$1") (pin "P$2") (pinfunction "P$2_P$2") (pintype "bidirectional"))
    )
    (net (code "71") (name "Net-(JP2-Pad4)") (class "Default")
      (node (ref "JP2") (pin "4") (pinfunction "4_4") (pintype "passive"))
      (node (ref "R49") (pin "2") (pinfunction "2_2") (pintype "passive"))
      (node (ref "U$1") (pin "P$49") (pinfunction "P$49_P$49") (pintype "bidirectional"))
    )
    (net (code "72") (name "Net-(JP2-Pad5)") (class "Default")
      (node (ref "JP2") (pin "5") (pinfunction "5_5") (pintype "passive"))
      (node (ref "R3") (pin "1") (pinfunction "1_1") (pintype "passive"))
      (node (ref "R67") (pin "1") (pinfunction "1_1") (pintype "passive"))
      (node (ref "U$1") (pin "P$3") (pinfunction "P$3_P$3") (pintype "bidirectional"))
    )
    (net (code "73") (name "Net-(JP2-Pad6)") (class "Default")
      (node (ref "JP2") (pin "6") (pinfunction "6_6") (pintype "passive"))
      (node (ref "R48") (pin "2") (pinfunction "2_2") (pintype "passive"))
      (node (ref "R72") (pin "1") (pinfunction "1_1") (pintype "passive"))
      (node (ref "U$1") (pin "P$48") (pinfunction "P$48_P$48") (pintype "bidirectional"))
    )
    (net (code "74") (name "Net-(JP2-Pad7)") (class "Default")
      (node (ref "JP2") (pin "7") (pinfunction "7_7") (pintype "passive"))
      (node (ref "R4") (pin "1") (pinfunction "1_1") (pintype "passive"))
      (node (ref "R66") (pin "1") (pinfunction "1_1") (pintype "passive"))
      (node (ref "U$1") (pin "P$4") (pinfunction "P$4_P$4") (pintype "bidirectional"))
    )
    (net (code "75") (name "Net-(JP2-Pad8)") (class "Default")
      (node (ref "JP2") (pin "8") (pinfunction "8_8") (pintype "passive"))
      (node (ref "R47") (pin "2") (pinfunction "2_2") (pintype "passive"))
      (node (ref "R73") (pin "1") (pinfunction "1_1") (pintype "passive"))
      (node (ref "U$1") (pin "P$47") (pinfunction "P$47_P$47") (pintype "bidirectional"))
    )
    (net (code "76") (name "Net-(JP2-Pad9)") (class "Default")
      (node (ref "JP2") (pin "9") (pinfunction "9_9") (pintype "passive"))
      (node (ref "R5") (pin "1") (pinfunction "1_1") (pintype "passive"))
      (node (ref "R65") (pin "1") (pinfunction "1_1") (pintype "passive"))
      (node (ref "U$1") (pin "P$5") (pinfunction "P$5_P$5") (pintype "bidirectional"))
    )
    (net (code "77") (name "Net-(JP2-Pad10)") (class "Default")
      (node (ref "JP2") (pin "10") (pinfunction "10_10") (pintype "passive"))
      (node (ref "R46") (pin "2") (pinfunction "2_2") (pintype "passive"))
      (node (ref "R74") (pin "1") (pinfunction "1_1") (pintype "passive"))
      (node (ref "U$1") (pin "P$46") (pinfunction "P$46_P$46") (pintype "bidirectional"))
    )
    (net (code "78") (name "Net-(JP2-Pad11)") (class "Default")
      (node (ref "JP2") (pin "11") (pinfunction "11_11") (pintype "passive"))
      (node (ref "R6") (pin "1") (pinfunction "1_1") (pintype "passive"))
      (node (ref "R64") (pin "1") (pinfunction "1_1") (pintype "passive"))
      (node (ref "U$1") (pin "P$6") (pinfunction "P$6_P$6") (pintype "bidirectional"))
    )
    (net (code "79") (name "Net-(JP2-Pad12)") (class "Default")
      (node (ref "JP2") (pin "12") (pinfunction "12_12") (pintype "passive"))
      (node (ref "R45") (pin "2") (pinfunction "2_2") (pintype "passive"))
      (node (ref "R75") (pin "1") (pinfunction "1_1") (pintype "passive"))
      (node (ref "U$1") (pin "P$45") (pinfunction "P$45_P$45") (pintype "bidirectional"))
    )
    (net (code "80") (name "Net-(JP2-Pad13)") (class "Default")
      (node (ref "JP2") (pin "13") (pinfunction "13_13") (pintype "passive"))
      (node (ref "R63") (pin "1") (pinfunction "1_1") (pintype "passive"))
      (node (ref "R7") (pin "1") (pinfunction "1_1") (pintype "passive"))
      (node (ref "U$1") (pin "P$7") (pinfunction "P$7_P$7") (pintype "bidirectional"))
    )
    (net (code "81") (name "Net-(JP2-Pad14)") (class "Default")
      (node (ref "JP2") (pin "14") (pinfunction "14_14") (pintype "passive"))
      (node (ref "R44") (pin "2") (pinfunction "2_2") (pintype "passive"))
      (node (ref "R76") (pin "1") (pinfunction "1_1") (pintype "passive"))
      (node (ref "U$1") (pin "P$44") (pinfunction "P$44_P$44") (pintype "bidirectional"))
    )
    (net (code "82") (name "Net-(JP2-Pad15)") (class "Default")
      (node (ref "JP2") (pin "15") (pinfunction "15_15") (pintype "passive"))
      (node (ref "R62") (pin "1") (pinfunction "1_1") (pintype "passive"))
      (node (ref "R8") (pin "1") (pinfunction "1_1") (pintype "passive"))
      (node (ref "U$1") (pin "P$8") (pinfunction "P$8_P$8") (pintype "bidirectional"))
    )
    (net (code "83") (name "Net-(JP2-Pad16)") (class "Default")
      (node (ref "JP2") (pin "16") (pinfunction "16_16") (pintype "passive"))
      (node (ref "R43") (pin "2") (pinfunction "2_2") (pintype "passive"))
      (node (ref "R77") (pin "1") (pinfunction "1_1") (pintype "passive"))
      (node (ref "U$1") (pin "P$43") (pinfunction "P$43_P$43") (pintype "bidirectional"))
    )
    (net (code "84") (name "Net-(JP2-Pad17)") (class "Default")
      (node (ref "JP2") (pin "17") (pinfunction "17_17") (pintype "passive"))
      (node (ref "R61") (pin "1") (pinfunction "1_1") (pintype "passive"))
      (node (ref "R9") (pin "1") (pinfunction "1_1") (pintype "passive"))
      (node (ref "U$1") (pin "P$9") (pinfunction "P$9_P$9") (pintype "bidirectional"))
    )
    (net (code "85") (name "Net-(JP2-Pad18)") (class "Default")
      (node (ref "JP2") (pin "18") (pinfunction "18_18") (pintype "passive"))
      (node (ref "R42") (pin "2") (pinfunction "2_2") (pintype "passive"))
      (node (ref "R78") (pin "1") (pinfunction "1_1") (pintype "passive"))
      (node (ref "U$1") (pin "P$42") (pinfunction "P$42_P$42") (pintype "bidirectional"))
    )
    (net (code "86") (name "Net-(JP3-Pad1)") (class "Default")
      (node (ref "JP3") (pin "1") (pinfunction "1_1") (pintype "passive"))
      (node (ref "JP5") (pin "2") (pinfunction "2_2") (pintype "passive"))
    )
    (net (code "87") (name "Net-(JP3-Pad2)") (class "Default")
      (node (ref "JP3") (pin "2") (pinfunction "2_2") (pintype "passive"))
      (node (ref "JP4") (pin "2") (pinfunction "2_2") (pintype "passive"))
    )
    (net (code "88") (name "Net-(LED1-PadA)") (class "Default")
      (node (ref "LED1") (pin "A") (pinfunction "A_A") (pintype "passive"))
      (node (ref "R69") (pin "2") (pinfunction "2_2") (pintype "passive"))
    )
    (net (code "89") (name "Net-(LED2-PadC)") (class "Default")
      (node (ref "LED2") (pin "C") (pinfunction "C_C") (pintype "passive"))
      (node (ref "R70") (pin "1") (pinfunction "1_1") (pintype "passive"))
    )
    (net (code "90") (name "Net-(LED5-PadC)") (class "Default")
      (node (ref "LED5") (pin "C") (pinfunction "C_C") (pintype "passive"))
      (node (ref "R88") (pin "1") (pinfunction "1_1") (pintype "passive"))
    )
    (net (code "91") (name "Net-(LED6-PadC)") (class "Default")
      (node (ref "LED6") (pin "C") (pinfunction "C_C") (pintype "passive"))
      (node (ref "R89") (pin "1") (pinfunction "1_1") (pintype "passive"))
    )
    (net (code "92") (name "Net-(LED7-PadC)") (class "Default")
      (node (ref "LED7") (pin "C") (pinfunction "C_C") (pintype "passive"))
      (node (ref "R90") (pin "1") (pinfunction "1_1") (pintype "passive"))
    )
    (net (code "93") (name "Net-(Q1-D)") (class "Default")
      (node (ref "Q1") (pin "3") (pinfunction "D_3") (pintype "passive"))
      (node (ref "R51") (pin "2") (pinfunction "2_2") (pintype "passive"))
      (node (ref "U$2") (pin "49") (pinfunction "IOB_47_SS_49") (pintype "bidirectional"))
    )
    (net (code "94") (name "Net-(Q2-D)") (class "Default")
      (node (ref "Q2") (pin "3") (pinfunction "D_3") (pintype "passive"))
      (node (ref "R52") (pin "2") (pinfunction "2_2") (pintype "passive"))
      (node (ref "U$2") (pin "44") (pinfunction "CRESET_B_44") (pintype "bidirectional"))
    )
    (net (code "95") (name "Net-(R1-Pad2)") (class "Default")
      (node (ref "R1") (pin "2") (pinfunction "2_2") (pintype "passive"))
      (node (ref "U$3") (pin "P$1") (pinfunction "P$1_P$1") (pintype "bidirectional"))
    )
    (net (code "96") (name "Net-(R2-Pad2)") (class "Default")
      (node (ref "R2") (pin "2") (pinfunction "2_2") (pintype "passive"))
      (node (ref "U$3") (pin "P$2") (pinfunction "P$2_P$2") (pintype "bidirectional"))
    )
    (net (code "97") (name "Net-(R3-Pad2)") (class "Default")
      (node (ref "R3") (pin "2") (pinfunction "2_2") (pintype "passive"))
      (node (ref "U$3") (pin "P$3") (pinfunction "P$3_P$3") (pintype "bidirectional"))
    )
    (net (code "98") (name "Net-(R4-Pad2)") (class "Default")
      (node (ref "R4") (pin "2") (pinfunction "2_2") (pintype "passive"))
      (node (ref "U$3") (pin "P$4") (pinfunction "P$4_P$4") (pintype "bidirectional"))
    )
    (net (code "99") (name "Net-(R5-Pad2)") (class "Default")
      (node (ref "R5") (pin "2") (pinfunction "2_2") (pintype "passive"))
      (node (ref "U$3") (pin "P$5") (pinfunction "P$5_P$5") (pintype "bidirectional"))
    )
    (net (code "100") (name "Net-(R6-Pad2)") (class "Default")
      (node (ref "R6") (pin "2") (pinfunction "2_2") (pintype "passive"))
      (node (ref "U$3") (pin "P$6") (pinfunction "P$6_P$6") (pintype "bidirectional"))
    )
    (net (code "101") (name "Net-(R7-Pad2)") (class "Default")
      (node (ref "R7") (pin "2") (pinfunction "2_2") (pintype "passive"))
      (node (ref "U$3") (pin "P$7") (pinfunction "P$7_P$7") (pintype "bidirectional"))
    )
    (net (code "102") (name "Net-(R8-Pad2)") (class "Default")
      (node (ref "R8") (pin "2") (pinfunction "2_2") (pintype "passive"))
      (node (ref "U$3") (pin "P$8") (pinfunction "P$8_P$8") (pintype "bidirectional"))
    )
    (net (code "103") (name "Net-(R9-Pad2)") (class "Default")
      (node (ref "R9") (pin "2") (pinfunction "2_2") (pintype "passive"))
      (node (ref "U$3") (pin "P$9") (pinfunction "P$9_P$9") (pintype "bidirectional"))
    )
    (net (code "104") (name "Net-(R10-Pad2)") (class "Default")
      (node (ref "R10") (pin "2") (pinfunction "2_2") (pintype "passive"))
      (node (ref "U$3") (pin "P$10") (pinfunction "P$10_P$10") (pintype "bidirectional"))
    )
    (net (code "105") (name "Net-(R11-Pad2)") (class "Default")
      (node (ref "R11") (pin "2") (pinfunction "2_2") (pintype "passive"))
      (node (ref "U$3") (pin "P$11") (pinfunction "P$11_P$11") (pintype "bidirectional"))
    )
    (net (code "106") (name "Net-(R12-Pad2)") (class "Default")
      (node (ref "R12") (pin "2") (pinfunction "2_2") (pintype "passive"))
      (node (ref "U$3") (pin "P$12") (pinfunction "P$12_P$12") (pintype "bidirectional"))
    )
    (net (code "107") (name "Net-(R13-Pad2)") (class "Default")
      (node (ref "R13") (pin "2") (pinfunction "2_2") (pintype "passive"))
      (node (ref "U$3") (pin "P$13") (pinfunction "P$13_P$13") (pintype "bidirectional"))
    )
    (net (code "108") (name "Net-(R14-Pad2)") (class "Default")
      (node (ref "R14") (pin "2") (pinfunction "2_2") (pintype "passive"))
      (node (ref "U$3") (pin "P$14") (pinfunction "P$14_P$14") (pintype "bidirectional"))
    )
    (net (code "109") (name "Net-(R15-Pad2)") (class "Default")
      (node (ref "R15") (pin "2") (pinfunction "2_2") (pintype "passive"))
      (node (ref "U$3") (pin "P$15") (pinfunction "P$15_P$15") (pintype "bidirectional"))
    )
    (net (code "110") (name "Net-(R16-Pad2)") (class "Default")
      (node (ref "R16") (pin "2") (pinfunction "2_2") (pintype "passive"))
      (node (ref "U$3") (pin "P$16") (pinfunction "P$16_P$16") (pintype "bidirectional"))
    )
    (net (code "111") (name "Net-(R17-Pad2)") (class "Default")
      (node (ref "R17") (pin "2") (pinfunction "2_2") (pintype "passive"))
      (node (ref "U$3") (pin "P$17") (pinfunction "P$17_P$17") (pintype "bidirectional"))
    )
    (net (code "112") (name "Net-(R18-Pad1)") (class "Default")
      (node (ref "R18") (pin "1") (pinfunction "1_1") (pintype "passive"))
      (node (ref "U$1") (pin "P$18") (pinfunction "P$18_P$18") (pintype "bidirectional"))
    )
    (net (code "113") (name "Net-(R18-Pad2)") (class "Default")
      (node (ref "R18") (pin "2") (pinfunction "2_2") (pintype "passive"))
      (node (ref "U$3") (pin "P$18") (pinfunction "P$18_P$18") (pintype "bidirectional"))
    )
    (net (code "114") (name "Net-(R19-Pad1)") (class "Default")
      (node (ref "R19") (pin "1") (pinfunction "1_1") (pintype "passive"))
      (node (ref "U$1") (pin "P$19") (pinfunction "P$19_P$19") (pintype "bidirectional"))
    )
    (net (code "115") (name "Net-(R19-Pad2)") (class "Default")
      (node (ref "R19") (pin "2") (pinfunction "2_2") (pintype "passive"))
      (node (ref "U$3") (pin "P$19") (pinfunction "P$19_P$19") (pintype "bidirectional"))
    )
    (net (code "116") (name "Net-(R20-Pad1)") (class "Default")
      (node (ref "R20") (pin "1") (pinfunction "1_1") (pintype "passive"))
      (node (ref "U$1") (pin "P$20") (pinfunction "P$20_P$20") (pintype "bidirectional"))
    )
    (net (code "117") (name "Net-(R20-Pad2)") (class "Default")
      (node (ref "R20") (pin "2") (pinfunction "2_2") (pintype "passive"))
      (node (ref "U$3") (pin "P$20") (pinfunction "P$20_P$20") (pintype "bidirectional"))
    )
    (net (code "118") (name "Net-(R21-Pad1)") (class "Default")
      (node (ref "R21") (pin "1") (pinfunction "1_1") (pintype "passive"))
      (node (ref "U$1") (pin "P$21") (pinfunction "P$21_P$21") (pintype "bidirectional"))
    )
    (net (code "119") (name "Net-(R21-Pad2)") (class "Default")
      (node (ref "R21") (pin "2") (pinfunction "2_2") (pintype "passive"))
      (node (ref "U$3") (pin "P$21") (pinfunction "P$21_P$21") (pintype "bidirectional"))
    )
    (net (code "120") (name "Net-(R22-Pad1)") (class "Default")
      (node (ref "R22") (pin "1") (pinfunction "1_1") (pintype "passive"))
      (node (ref "U$1") (pin "P$22") (pinfunction "P$22_P$22") (pintype "bidirectional"))
    )
    (net (code "121") (name "Net-(R22-Pad2)") (class "Default")
      (node (ref "R22") (pin "2") (pinfunction "2_2") (pintype "passive"))
      (node (ref "U$3") (pin "P$22") (pinfunction "P$22_P$22") (pintype "bidirectional"))
    )
    (net (code "122") (name "Net-(R23-Pad1)") (class "Default")
      (node (ref "R23") (pin "1") (pinfunction "1_1") (pintype "passive"))
      (node (ref "U$1") (pin "P$23") (pinfunction "P$23_P$23") (pintype "bidirectional"))
    )
    (net (code "123") (name "Net-(R23-Pad2)") (class "Default")
      (node (ref "R23") (pin "2") (pinfunction "2_2") (pintype "passive"))
      (node (ref "U$3") (pin "P$23") (pinfunction "P$23_P$23") (pintype "bidirectional"))
    )
    (net (code "124") (name "Net-(R24-Pad1)") (class "Default")
      (node (ref "R24") (pin "1") (pinfunction "1_1") (pintype "passive"))
      (node (ref "U$1") (pin "P$24") (pinfunction "P$24_P$24") (pintype "bidirectional"))
    )
    (net (code "125") (name "Net-(R24-Pad2)") (class "Default")
      (node (ref "R24") (pin "2") (pinfunction "2_2") (pintype "passive"))
      (node (ref "U$3") (pin "P$24") (pinfunction "P$24_P$24") (pintype "bidirectional"))
    )
    (net (code "126") (name "Net-(R25-Pad1)") (class "Default")
      (node (ref "R25") (pin "1") (pinfunction "1_1") (pintype "passive"))
      (node (ref "U$1") (pin "P$25") (pinfunction "P$25_P$25") (pintype "bidirectional"))
    )
    (net (code "127") (name "Net-(R25-Pad2)") (class "Default")
      (node (ref "R25") (pin "2") (pinfunction "2_2") (pintype "passive"))
      (node (ref "U$3") (pin "P$25") (pinfunction "P$25_P$25") (pintype "bidirectional"))
    )
    (net (code "128") (name "Net-(R26-Pad1)") (class "Default")
      (node (ref "R26") (pin "1") (pinfunction "1_1") (pintype "passive"))
      (node (ref "U$3") (pin "P$26") (pinfunction "P$26_P$26") (pintype "bidirectional"))
    )
    (net (code "129") (name "Net-(R26-Pad2)") (class "Default")
      (node (ref "R26") (pin "2") (pinfunction "2_2") (pintype "passive"))
      (node (ref "U$1") (pin "P$26") (pinfunction "P$26_P$26") (pintype "bidirectional"))
    )
    (net (code "130") (name "Net-(R27-Pad1)") (class "Default")
      (node (ref "R27") (pin "1") (pinfunction "1_1") (pintype "passive"))
      (node (ref "U$3") (pin "P$27") (pinfunction "P$27_P$27") (pintype "bidirectional"))
    )
    (net (code "131") (name "Net-(R27-Pad2)") (class "Default")
      (node (ref "R27") (pin "2") (pinfunction "2_2") (pintype "passive"))
      (node (ref "U$1") (pin "P$27") (pinfunction "P$27_P$27") (pintype "bidirectional"))
    )
    (net (code "132") (name "Net-(R28-Pad1)") (class "Default")
      (node (ref "R28") (pin "1") (pinfunction "1_1") (pintype "passive"))
      (node (ref "U$3") (pin "P$28") (pinfunction "P$28_P$28") (pintype "bidirectional"))
    )
    (net (code "133") (name "Net-(R28-Pad2)") (class "Default")
      (node (ref "R28") (pin "2") (pinfunction "2_2") (pintype "passive"))
      (node (ref "U$1") (pin "P$28") (pinfunction "P$28_P$28") (pintype "bidirectional"))
    )
    (net (code "134") (name "Net-(R29-Pad1)") (class "Default")
      (node (ref "R29") (pin "1") (pinfunction "1_1") (pintype "passive"))
      (node (ref "U$3") (pin "P$29") (pinfunction "P$29_P$29") (pintype "bidirectional"))
    )
    (net (code "135") (name "Net-(R29-Pad2)") (class "Default")
      (node (ref "R29") (pin "2") (pinfunction "2_2") (pintype "passive"))
      (node (ref "U$1") (pin "P$29") (pinfunction "P$29_P$29") (pintype "bidirectional"))
    )
    (net (code "136") (name "Net-(R30-Pad1)") (class "Default")
      (node (ref "R30") (pin "1") (pinfunction "1_1") (pintype "passive"))
      (node (ref "U$3") (pin "P$30") (pinfunction "P$30_P$30") (pintype "bidirectional"))
    )
    (net (code "137") (name "Net-(R30-Pad2)") (class "Default")
      (node (ref "R30") (pin "2") (pinfunction "2_2") (pintype "passive"))
      (node (ref "U$1") (pin "P$30") (pinfunction "P$30_P$30") (pintype "bidirectional"))
    )
    (net (code "138") (name "Net-(R31-Pad1)") (class "Default")
      (node (ref "R31") (pin "1") (pinfunction "1_1") (pintype "passive"))
      (node (ref "U$3") (pin "P$31") (pinfunction "P$31_P$31") (pintype "bidirectional"))
    )
    (net (code "139") (name "Net-(R31-Pad2)") (class "Default")
      (node (ref "R31") (pin "2") (pinfunction "2_2") (pintype "passive"))
      (node (ref "U$1") (pin "P$31") (pinfunction "P$31_P$31") (pintype "bidirectional"))
    )
    (net (code "140") (name "Net-(R32-Pad1)") (class "Default")
      (node (ref "R32") (pin "1") (pinfunction "1_1") (pintype "passive"))
      (node (ref "U$3") (pin "P$32") (pinfunction "P$32_P$32") (pintype "bidirectional"))
    )
    (net (code "141") (name "Net-(R32-Pad2)") (class "Default")
      (node (ref "R32") (pin "2") (pinfunction "2_2") (pintype "passive"))
      (node (ref "U$1") (pin "P$32") (pinfunction "P$32_P$32") (pintype "bidirectional"))
    )
    (net (code "142") (name "Net-(R33-Pad1)") (class "Default")
      (node (ref "R33") (pin "1") (pinfunction "1_1") (pintype "passive"))
      (node (ref "U$3") (pin "P$33") (pinfunction "P$33_P$33") (pintype "bidirectional"))
    )
    (net (code "143") (name "Net-(R33-Pad2)") (class "Default")
      (node (ref "R33") (pin "2") (pinfunction "2_2") (pintype "passive"))
      (node (ref "U$1") (pin "P$33") (pinfunction "P$33_P$33") (pintype "bidirectional"))
    )
    (net (code "144") (name "Net-(R34-Pad1)") (class "Default")
      (node (ref "R34") (pin "1") (pinfunction "1_1") (pintype "passive"))
      (node (ref "U$3") (pin "P$34") (pinfunction "P$34_P$34") (pintype "bidirectional"))
    )
    (net (code "145") (name "Net-(R35-Pad1)") (class "Default")
      (node (ref "R35") (pin "1") (pinfunction "1_1") (pintype "passive"))
      (node (ref "U$3") (pin "P$35") (pinfunction "P$35_P$35") (pintype "bidirectional"))
    )
    (net (code "146") (name "Net-(R36-Pad1)") (class "Default")
      (node (ref "R36") (pin "1") (pinfunction "1_1") (pintype "passive"))
      (node (ref "U$3") (pin "P$36") (pinfunction "P$36_P$36") (pintype "bidirectional"))
    )
    (net (code "147") (name "Net-(R37-Pad1)") (class "Default")
      (node (ref "R37") (pin "1") (pinfunction "1_1") (pintype "passive"))
      (node (ref "U$3") (pin "P$37") (pinfunction "P$37_P$37") (pintype "bidirectional"))
    )
    (net (code "148") (name "Net-(R38-Pad1)") (class "Default")
      (node (ref "R38") (pin "1") (pinfunction "1_1") (pintype "passive"))
      (node (ref "U$3") (pin "P$38") (pinfunction "P$38_P$38") (pintype "bidirectional"))
    )
    (net (code "149") (name "Net-(R39-Pad1)") (class "Default")
      (node (ref "R39") (pin "1") (pinfunction "1_1") (pintype "passive"))
      (node (ref "U$3") (pin "P$39") (pinfunction "P$39_P$39") (pintype "bidirectional"))
    )
    (net (code "150") (name "Net-(R40-Pad1)") (class "Default")
      (node (ref "R40") (pin "1") (pinfunction "1_1") (pintype "passive"))
      (node (ref "U$3") (pin "P$40") (pinfunction "P$40_P$40") (pintype "bidirectional"))
    )
    (net (code "151") (name "Net-(R41-Pad1)") (class "Default")
      (node (ref "R41") (pin "1") (pinfunction "1_1") (pintype "passive"))
      (node (ref "U$3") (pin "P$41") (pinfunction "P$41_P$41") (pintype "bidirectional"))
    )
    (net (code "152") (name "Net-(R42-Pad1)") (class "Default")
      (node (ref "R42") (pin "1") (pinfunction "1_1") (pintype "passive"))
      (node (ref "U$3") (pin "P$42") (pinfunction "P$42_P$42") (pintype "bidirectional"))
    )
    (net (code "153") (name "Net-(R43-Pad1)") (class "Default")
      (node (ref "R43") (pin "1") (pinfunction "1_1") (pintype "passive"))
      (node (ref "U$3") (pin "P$43") (pinfunction "P$43_P$43") (pintype "bidirectional"))
    )
    (net (code "154") (name "Net-(R44-Pad1)") (class "Default")
      (node (ref "R44") (pin "1") (pinfunction "1_1") (pintype "passive"))
      (node (ref "U$3") (pin "P$44") (pinfunction "P$44_P$44") (pintype "bidirectional"))
    )
    (net (code "155") (name "Net-(R45-Pad1)") (class "Default")
      (node (ref "R45") (pin "1") (pinfunction "1_1") (pintype "passive"))
      (node (ref "U$3") (pin "P$45") (pinfunction "P$45_P$45") (pintype "bidirectional"))
    )
    (net (code "156") (name "Net-(R46-Pad1)") (class "Default")
      (node (ref "R46") (pin "1") (pinfunction "1_1") (pintype "passive"))
      (node (ref "U$3") (pin "P$46") (pinfunction "P$46_P$46") (pintype "bidirectional"))
    )
    (net (code "157") (name "Net-(R47-Pad1)") (class "Default")
      (node (ref "R47") (pin "1") (pinfunction "1_1") (pintype "passive"))
      (node (ref "U$3") (pin "P$47") (pinfunction "P$47_P$47") (pintype "bidirectional"))
    )
    (net (code "158") (name "Net-(R48-Pad1)") (class "Default")
      (node (ref "R48") (pin "1") (pinfunction "1_1") (pintype "passive"))
      (node (ref "U$3") (pin "P$48") (pinfunction "P$48_P$48") (pintype "bidirectional"))
    )
    (net (code "159") (name "Net-(R49-Pad1)") (class "Default")
      (node (ref "R49") (pin "1") (pinfunction "1_1") (pintype "passive"))
      (node (ref "U$3") (pin "P$49") (pinfunction "P$49_P$49") (pintype "bidirectional"))
    )
    (net (code "160") (name "Net-(R50-Pad1)") (class "Default")
      (node (ref "R50") (pin "1") (pinfunction "1_1") (pintype "passive"))
      (node (ref "U$3") (pin "P$50") (pinfunction "P$50_P$50") (pintype "bidirectional"))
    )
    (net (code "161") (name "Net-(U$2E-CDONE)") (class "Default")
      (node (ref "R68") (pin "1") (pinfunction "1_1") (pintype "passive"))
      (node (ref "R69") (pin "1") (pinfunction "1_1") (pintype "passive"))
      (node (ref "U$2") (pin "43") (pinfunction "CDONE_43") (pintype "bidirectional"))
    )
    (net (code "162") (name "unconnected-(JP1-Pad17)") (class "Default")
      (node (ref "JP1") (pin "17") (pinfunction "17_17") (pintype "passive"))
    )
    (net (code "163") (name "unconnected-(JP1-Pad18)") (class "Default")
      (node (ref "JP1") (pin "18") (pinfunction "18_18") (pintype "passive"))
    )
    (net (code "164") (name "unconnected-(JP3-Pad3)") (class "Default")
      (node (ref "JP3") (pin "3") (pinfunction "3_3") (pintype "passive"))
    )
    (net (code "165") (name "unconnected-(JP3-Pad4)") (class "Default")
      (node (ref "JP3") (pin "4") (pinfunction "4_4") (pintype "passive"))
    )
    (net (code "166") (name "unconnected-(JP3-Pad5)") (class "Default")
      (node (ref "JP3") (pin "5") (pinfunction "5_5") (pintype "passive"))
    )
    (net (code "167") (name "unconnected-(JP3-Pad8)") (class "Default")
      (node (ref "JP3") (pin "8") (pinfunction "8_8") (pintype "passive"))
    )
    (net (code "168") (name "unconnected-(JP3-Pad10)") (class "Default")
      (node (ref "JP3") (pin "10") (pinfunction "10_10") (pintype "passive"))
    )
    (net (code "169") (name "unconnected-(JP3-Pad11)") (class "Default")
      (node (ref "JP3") (pin "11") (pinfunction "11_11") (pintype "passive"))
    )
    (net (code "170") (name "unconnected-(JP3-Pad12)") (class "Default")
      (node (ref "JP3") (pin "12") (pinfunction "12_12") (pintype "passive"))
    )
    (net (code "171") (name "unconnected-(JP3-Pad13)") (class "Default")
      (node (ref "JP3") (pin "13") (pinfunction "13_13") (pintype "passive"))
    )
    (net (code "172") (name "unconnected-(JP3-Pad15)") (class "Default")
      (node (ref "JP3") (pin "15") (pinfunction "15_15") (pintype "passive"))
    )
    (net (code "173") (name "unconnected-(JP3-Pad16)") (class "Default")
      (node (ref "JP3") (pin "16") (pinfunction "16_16") (pintype "passive"))
    )
    (net (code "174") (name "unconnected-(JP3-Pad17)") (class "Default")
      (node (ref "JP3") (pin "17") (pinfunction "17_17") (pintype "passive"))
    )
    (net (code "175") (name "unconnected-(JP3-Pad26)") (class "Default")
      (node (ref "JP3") (pin "26") (pinfunction "26_26") (pintype "passive"))
    )
    (net (code "176") (name "unconnected-(U$2A-IOT_73-Pad78)") (class "Default")
      (node (ref "U$2") (pin "78") (pinfunction "IOT_73_78") (pintype "bidirectional"))
    )
    (net (code "177") (name "unconnected-(U$2A-IOT_74-Pad79)") (class "Default")
      (node (ref "U$2") (pin "79") (pinfunction "IOT_74_79") (pintype "bidirectional"))
    )
    (net (code "178") (name "unconnected-(U$2A-IOT_77-Pad81)") (class "Default")
      (node (ref "U$2") (pin "81") (pinfunction "IOT_77_81") (pintype "bidirectional"))
    )
    (net (code "179") (name "unconnected-(U$2A-IOT_80-Pad85)") (class "Default")
      (node (ref "U$2") (pin "85") (pinfunction "IOT_80_85") (pintype "bidirectional"))
    )
    (net (code "180") (name "unconnected-(U$2A-IOT_87-Pad93)") (class "Default")
      (node (ref "U$2") (pin "93") (pinfunction "IOT_87_93") (pintype "bidirectional"))
    )
    (net (code "181") (name "unconnected-(U$2A-IOT_90-Pad96)") (class "Default")
      (node (ref "U$2") (pin "96") (pinfunction "IOT_90_96") (pintype "bidirectional"))
    )
    (net (code "182") (name "unconnected-(U$2B-IOR_52-Pad51)") (class "Default")
      (node (ref "U$2") (pin "51") (pinfunction "IOR_52_51") (pintype "bidirectional"))
    )
    (net (code "183") (name "unconnected-(U$2B-IOR_53-Pad52)") (class "Default")
      (node (ref "U$2") (pin "52") (pinfunction "IOR_53_52") (pintype "bidirectional"))
    )
    (net (code "184") (name "unconnected-(U$2B-IOR_54-Pad53)") (class "Default")
      (node (ref "U$2") (pin "53") (pinfunction "IOR_54_53") (pintype "bidirectional"))
    )
    (net (code "185") (name "unconnected-(U$2B-IOR_55-Pad54)") (class "Default")
      (node (ref "U$2") (pin "54") (pinfunction "IOR_55_54") (pintype "bidirectional"))
    )
    (net (code "186") (name "unconnected-(U$2B-IOR_56-Pad56)") (class "Default")
      (node (ref "U$2") (pin "56") (pinfunction "IOR_56_56") (pintype "bidirectional"))
    )
    (net (code "187") (name "unconnected-(U$2B-IOR_57-Pad57)") (class "Default")
      (node (ref "U$2") (pin "57") (pinfunction "IOR_57_57") (pintype "bidirectional"))
    )
    (net (code "188") (name "unconnected-(U$2B-IOR_58-Pad59)") (class "Default")
      (node (ref "U$2") (pin "59") (pinfunction "IOR_58_59") (pintype "bidirectional"))
    )
    (net (code "189") (name "unconnected-(U$2B-IOR_59-Pad60)") (class "Default")
      (node (ref "U$2") (pin "60") (pinfunction "IOR_59_60") (pintype "bidirectional"))
    )
    (net (code "190") (name "unconnected-(U$2B-IOR_63-Pad64)") (class "Default")
      (node (ref "U$2") (pin "64") (pinfunction "IOR_63_64") (pintype "bidirectional"))
    )
    (net (code "191") (name "unconnected-(U$2B-IOR_64-Pad65)") (class "Default")
      (node (ref "U$2") (pin "65") (pinfunction "IOR_64_65") (pintype "bidirectional"))
    )
    (net (code "192") (name "unconnected-(U$2B-IOR_65-Pad66)") (class "Default")
      (node (ref "U$2") (pin "66") (pinfunction "IOR_65_66") (pintype "bidirectional"))
    )
    (net (code "193") (name "unconnected-(U$2B-IOR_67-Pad68)") (class "Default")
      (node (ref "U$2") (pin "68") (pinfunction "IOR_67_68") (pintype "bidirectional"))
    )
    (net (code "194") (name "unconnected-(U$2B-IOR_68-Pad69)") (class "Default")
      (node (ref "U$2") (pin "69") (pinfunction "IOR_68_69") (pintype "bidirectional"))
    )
    (net (code "195") (name "unconnected-(U$2B-IOR_69-Pad71)") (class "Default")
      (node (ref "U$2") (pin "71") (pinfunction "IOR_69_71") (pintype "bidirectional"))
    )
    (net (code "196") (name "unconnected-(U$2B-IOR_71-Pad73)") (class "Default")
      (node (ref "U$2") (pin "73") (pinfunction "IOR_71_73") (pintype "bidirectional"))
    )
    (net (code "197") (name "unconnected-(U$2C-IOB_35_GBIN5-Pad33)") (class "Default")
      (node (ref "U$2") (pin "33") (pinfunction "IOB_35_GBIN5_33") (pintype "bidirectional"))
    )
    (net (code "198") (name "unconnected-(U$2C-IOB_36_GBIN4-Pad34)") (class "Default")
      (node (ref "U$2") (pin "34") (pinfunction "IOB_36_GBIN4_34") (pintype "bidirectional"))
    )
    (net (code "199") (name "unconnected-(U$2C-IOB_41-Pad40)") (class "Default")
      (node (ref "U$2") (pin "40") (pinfunction "IOB_41_40") (pintype "bidirectional"))
    )
    (net (code "200") (name "unconnected-(U$2C-IOB_42_CBSEL0-Pad41)") (class "Default")
      (node (ref "U$2") (pin "41") (pinfunction "IOB_42_CBSEL0_41") (pintype "bidirectional"))
    )
    (net (code "201") (name "unconnected-(U$2C-IOB_43_CBSEL1-Pad42)") (class "Default")
      (node (ref "U$2") (pin "42") (pinfunction "IOB_43_CBSEL1_42") (pintype "bidirectional"))
    )
    (net (code "202") (name "unconnected-(U$2D-IOL_6B_GBIN7-Pad13)") (class "Default")
      (node (ref "U$2") (pin "13") (pinfunction "IOL_6B_GBIN7_13") (pintype "bidirectional"))
    )
    (net (code "203") (name "unconnected-(U$2D-IOL_7A_GBIN6-Pad15)") (class "Default")
      (node (ref "U$2") (pin "15") (pinfunction "IOL_7A_GBIN6_15") (pintype "bidirectional"))
    )
  )
)
